# SCH_EDR_Project_2023-04-19.net
KiCad netlist of a schematic drawn in EasyEDA
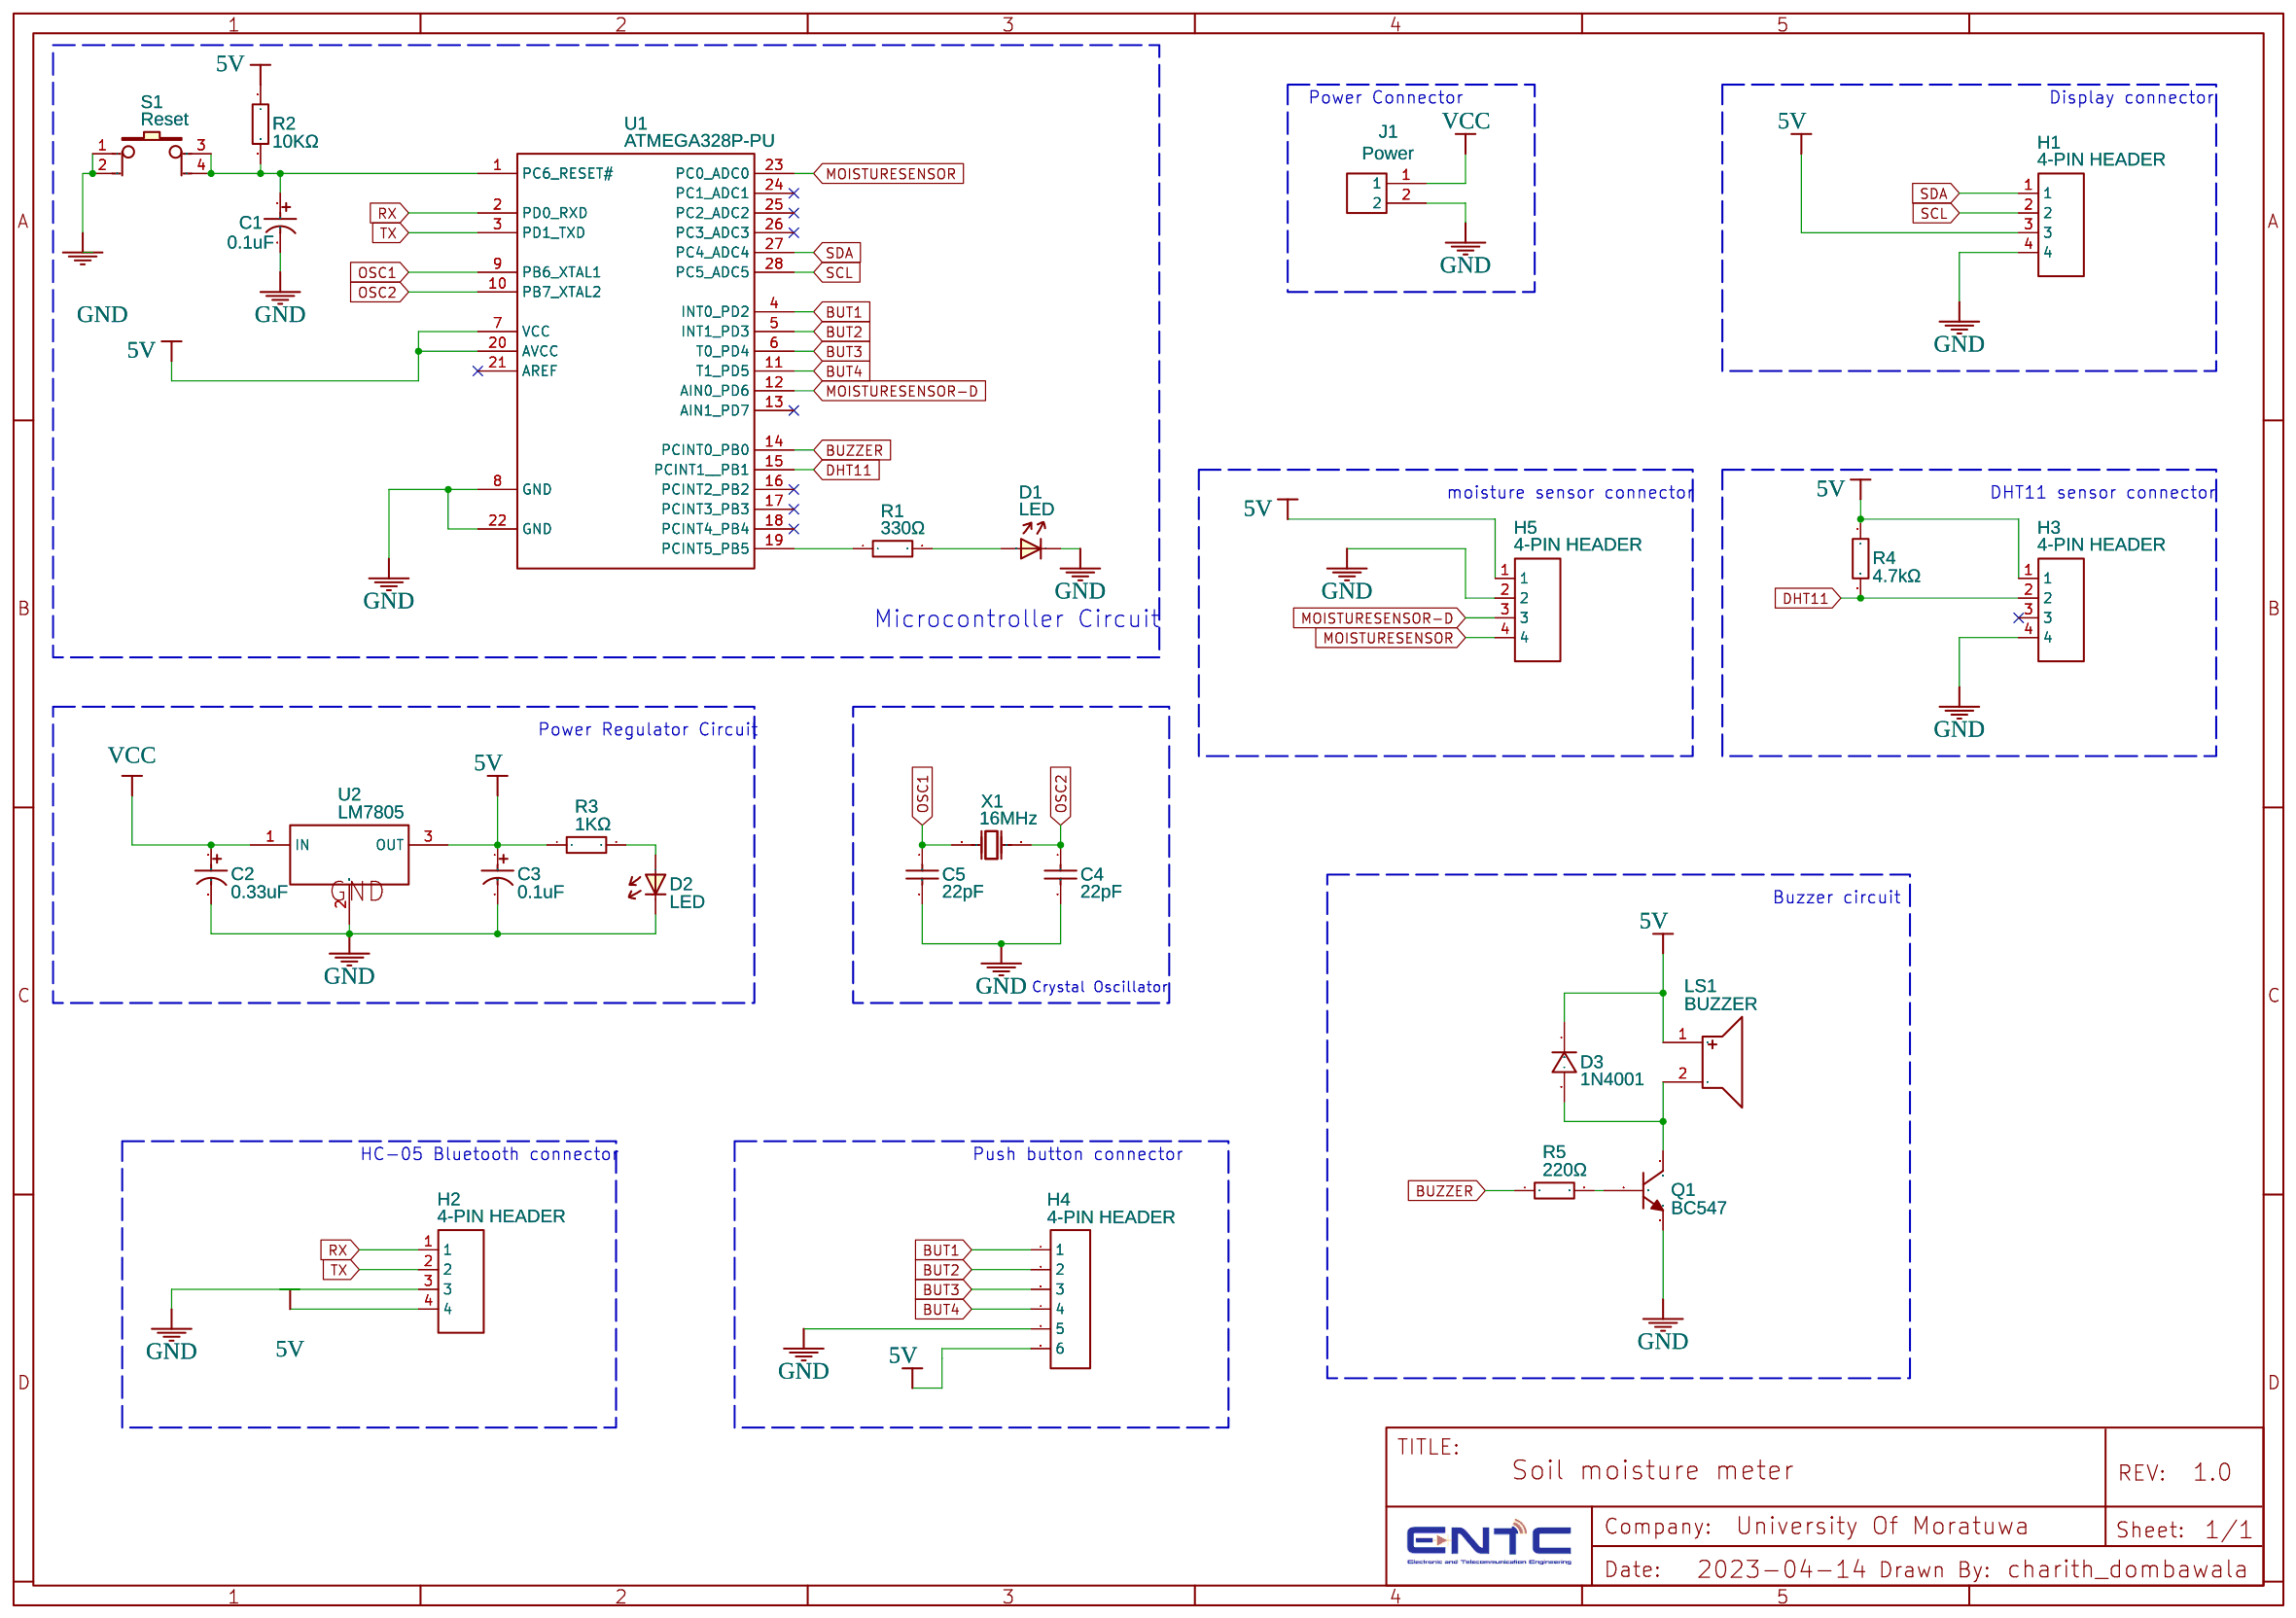
[diagram p0: schematic sheet]

(export (version "E")
  (design (tool "Eeschema 10.0.6"))
  (components
    (comp (ref "C1")
      (value "0.1uF")
      (fields (field (name "BOM_Manufacturer Part") "0.1UF 50V") (field (name "BOM_Supplier Part") "C28061"))
      (libsource (lib "") (part "0.1uF"))
    )
    (comp (ref "C2")
      (value "0.33uF")
      (fields
        (field (name "BOM_Manufacturer Part") "0.33uF 50V 5*11")
        (field (name "BOM_Supplier Part") "C45097")
      )
      (libsource (lib "") (part "0.33uF"))
    )
    (comp (ref "C3")
      (value "0.1uF")
      (fields (field (name "BOM_Manufacturer Part") "0.1UF 50V") (field (name "BOM_Supplier Part") "C28061"))
      (libsource (lib "") (part "0.1uF"))
    )
    (comp (ref "C4")
      (value "22pF")
      (fields
        (field (name "BOM_Manufacturer Part") "22pf/50V 10%")
        (field (name "BOM_Supplier Part") "C9316")
      )
      (libsource (lib "") (part "22pf/50V 10%"))
    )
    (comp (ref "C5")
      (value "22pF")
      (fields
        (field (name "BOM_Manufacturer Part") "22pf/50V 10%")
        (field (name "BOM_Supplier Part") "C9316")
      )
      (libsource (lib "") (part "22pf/50V 10%"))
    )
    (comp (ref "D1")
      (value "LED")
      (fields (field (name "Manufacturer Part") "5mm LED"))
      (libsource (lib "") (part "LED_1"))
    )
    (comp (ref "D2")
      (value "LED")
      (fields (field (name "Manufacturer Part") "5mm LED"))
      (libsource (lib "") (part "LED"))
    )
    (comp (ref "D3")
      (value "1N4001")
      (fields (field (name "BOM_Supplier Part") "C99656"))
      (libsource (lib "") (part "1N4001"))
    )
    (comp (ref "H1") (value "4-PIN HEADER") (libsource (lib "") (part "HEADER - HEADER-FEMALE-2.54_1X4")))
    (comp (ref "H2") (value "4-PIN HEADER") (libsource (lib "") (part "HEADER - HEADER-FEMALE-2.54_1X4")))
    (comp (ref "H3") (value "4-PIN HEADER") (libsource (lib "") (part "HEADER - HEADER-FEMALE-2.54_1X4")))
    (comp (ref "H4")
      (value "4-PIN HEADER")
      (fields (field (name "BOM_Supplier Part") "C40877"))
      (libsource (lib "") (part "HDR-F-2.54_1x6"))
    )
    (comp (ref "H5") (value "4-PIN HEADER") (libsource (lib "") (part "HEADER - HEADER-FEMALE-2.54_1X4")))
    (comp (ref "J1")
      (value "Power")
      (fields
        (field (name "BOM_Manufacturer Part") "XHB-2A Connector")
        (field (name "BOM_Supplier Part") "C57981")
      )
      (libsource (lib "") (part "JST_2 PIN"))
    )
    (comp (ref "LS1")
      (value "BUZZER")
      (fields
        (field (name "BOM_Manufacturer Part") "BUZZERHMB1206-03")
        (field (name "BOM_Supplier Part") "C96101")
      )
      (libsource (lib "") (part "BUZZER"))
    )
    (comp (ref "Q1")
      (value "BC547")
      (fields (field (name "BOM_Manufacturer Part") "BC547BTF") (field (name "BOM_Supplier Part") "C900798"))
      (libsource (lib "") (part "BC547BTF"))
    )
    (comp (ref "R1")
      (value "330Ω")
      (fields
        (field (name "BOM_Manufacturer Part") "MFR0W4F2200A50")
        (field (name "BOM_Supplier Part") "E57439")
      )
      (libsource (lib "") (part "RESISTOR"))
    )
    (comp (ref "R2")
      (value "10KΩ")
      (fields
        (field (name "BOM_Manufacturer Part") "MFR0W4F2200A50")
        (field (name "BOM_Supplier Part") "E57439")
      )
      (libsource (lib "") (part "RESISTOR_1"))
    )
    (comp (ref "R3")
      (value "1KΩ")
      (fields
        (field (name "BOM_Manufacturer Part") "MFR0W4F2200A50")
        (field (name "BOM_Supplier Part") "E57439")
      )
      (libsource (lib "") (part "RESISTOR"))
    )
    (comp (ref "R4")
      (value "4.7kΩ")
      (fields
        (field (name "BOM_Manufacturer Part") "MFR0W4F2200A50")
        (field (name "BOM_Supplier Part") "E57439")
      )
      (libsource (lib "") (part "RESISTOR_1"))
    )
    (comp (ref "R5")
      (value "220Ω")
      (fields
        (field (name "BOM_Manufacturer Part") "MFR0W4F2200A50")
        (field (name "BOM_Supplier Part") "E57439")
      )
      (libsource (lib "") (part "RESISTOR"))
    )
    (comp (ref "S1")
      (value "Reset")
      (fields
        (field (name "BOM_Manufacturer Part") "button6*6*8.5")
        (field (name "BOM_Supplier Part") "C59980")
      )
      (libsource (lib "") (part "Push_Button"))
    )
    (comp (ref "U1")
      (value "ATMEGA328P-PU")
      (fields (field (name "BOM_Supplier Part") "C33901"))
      (libsource (lib "") (part "ATMEGA328P-PU"))
    )
    (comp (ref "U2")
      (value "LM7805")
      (fields (field (name "BOM_Manufacturer Part") "L7805CV-DG") (field (name "BOM_Supplier Part") "C3795"))
      (libsource (lib "") (part "7805(TO-220)"))
    )
    (comp (ref "X1")
      (value "16MHz")
      (fields (field (name "BOM_Manufacturer Part") "ATS16A") (field (name "BOM_Supplier Part") "C1669847"))
      (libsource (lib "") (part "ATS16A"))
    )
  )
  (nets
    (net (code "1") (name "5V") (class "Default")
      (node (ref "C3") (pin "1") (pinfunction "1_1") (pintype "input"))
      (node (ref "D3") (pin "1") (pinfunction "C_1") (pintype "unspecified"))
      (node (ref "H1") (pin "3") (pinfunction "3_3") (pintype "unspecified"))
      (node (ref "H2") (pin "4") (pinfunction "4_4") (pintype "unspecified"))
      (node (ref "H3") (pin "1") (pinfunction "1_1") (pintype "unspecified"))
      (node (ref "H4") (pin "6") (pinfunction "6_6") (pintype "input"))
      (node (ref "H5") (pin "1") (pinfunction "1_1") (pintype "unspecified"))
      (node (ref "LS1") (pin "1") (pinfunction "1_1") (pintype "unspecified"))
      (node (ref "R2") (pin "1") (pinfunction "1_1") (pintype "input"))
      (node (ref "R3") (pin "1") (pinfunction "1_1") (pintype "input"))
      (node (ref "R4") (pin "1") (pinfunction "1_1") (pintype "input"))
      (node (ref "U1") (pin "20") (pinfunction "AVCC_20") (pintype "passive"))
      (node (ref "U1") (pin "7") (pinfunction "VCC_7") (pintype "passive"))
      (node (ref "U2") (pin "3") (pinfunction "OUT_3") (pintype "passive"))
    )
    (net (code "2") (name "BUT1") (class "Default")
      (node (ref "H4") (pin "1") (pinfunction "1_1") (pintype "input"))
      (node (ref "U1") (pin "4") (pinfunction "INT0_PD2_4") (pintype "bidirectional"))
    )
    (net (code "3") (name "BUT2") (class "Default")
      (node (ref "H4") (pin "2") (pinfunction "2_2") (pintype "input"))
      (node (ref "U1") (pin "5") (pinfunction "INT1_PD3_5") (pintype "bidirectional"))
    )
    (net (code "4") (name "BUT3") (class "Default")
      (node (ref "H4") (pin "3") (pinfunction "3_3") (pintype "input"))
      (node (ref "U1") (pin "6") (pinfunction "T0_PD4_6") (pintype "bidirectional"))
    )
    (net (code "5") (name "BUT4") (class "Default")
      (node (ref "H4") (pin "4") (pinfunction "4_4") (pintype "input"))
      (node (ref "U1") (pin "11") (pinfunction "T1_PD5_11") (pintype "bidirectional"))
    )
    (net (code "6") (name "BUZZER") (class "Default")
      (node (ref "R5") (pin "1") (pinfunction "1_1") (pintype "input"))
      (node (ref "U1") (pin "14") (pinfunction "PCINT0_PB0_14") (pintype "bidirectional"))
    )
    (net (code "7") (name "DHT11") (class "Default")
      (node (ref "H3") (pin "2") (pinfunction "2_2") (pintype "unspecified"))
      (node (ref "R4") (pin "2") (pinfunction "2_2") (pintype "input"))
      (node (ref "U1") (pin "15") (pinfunction "PCINT1__PB1_15") (pintype "bidirectional"))
    )
    (net (code "8") (name "GND") (class "Default")
      (node (ref "C1") (pin "2") (pinfunction "2_2") (pintype "input"))
      (node (ref "C2") (pin "2") (pinfunction "2_2") (pintype "input"))
      (node (ref "C3") (pin "2") (pinfunction "2_2") (pintype "input"))
      (node (ref "C4") (pin "2") (pinfunction "2_2") (pintype "input"))
      (node (ref "C5") (pin "2") (pinfunction "2_2") (pintype "input"))
      (node (ref "D1") (pin "2") (pinfunction "2_2") (pintype "unspecified"))
      (node (ref "D2") (pin "2") (pinfunction "2_2") (pintype "unspecified"))
      (node (ref "H1") (pin "4") (pinfunction "4_4") (pintype "unspecified"))
      (node (ref "H2") (pin "3") (pinfunction "3_3") (pintype "unspecified"))
      (node (ref "H3") (pin "4") (pinfunction "4_4") (pintype "unspecified"))
      (node (ref "H4") (pin "5") (pinfunction "5_5") (pintype "input"))
      (node (ref "H5") (pin "2") (pinfunction "2_2") (pintype "unspecified"))
      (node (ref "J1") (pin "2") (pinfunction "2_2") (pintype "unspecified"))
      (node (ref "Q1") (pin "3") (pinfunction "E_3") (pintype "unspecified"))
      (node (ref "S1") (pin "1") (pinfunction "1_1") (pintype "input"))
      (node (ref "S1") (pin "2") (pinfunction "2_2") (pintype "input"))
      (node (ref "U1") (pin "22") (pinfunction "GND_22") (pintype "passive"))
      (node (ref "U1") (pin "8") (pinfunction "GND_8") (pintype "passive"))
      (node (ref "U2") (pin "2") (pinfunction "GND_2") (pintype "passive"))
    )
    (net (code "9") (name "MOISTURESENSOR") (class "Default")
      (node (ref "H5") (pin "4") (pinfunction "4_4") (pintype "unspecified"))
      (node (ref "U1") (pin "23") (pinfunction "PC0_ADC0_23") (pintype "bidirectional"))
    )
    (net (code "10") (name "MOISTURESENSOR-D") (class "Default")
      (node (ref "H5") (pin "3") (pinfunction "3_3") (pintype "unspecified"))
      (node (ref "U1") (pin "12") (pinfunction "AIN0_PD6_12") (pintype "bidirectional"))
    )
    (net (code "11") (name "Net-(D1-Pad1)") (class "Default")
      (node (ref "D1") (pin "1") (pinfunction "1_1") (pintype "unspecified"))
      (node (ref "R1") (pin "2") (pinfunction "2_2") (pintype "input"))
    )
    (net (code "12") (name "Net-(D2-Pad1)") (class "Default")
      (node (ref "D2") (pin "1") (pinfunction "1_1") (pintype "unspecified"))
      (node (ref "R3") (pin "2") (pinfunction "2_2") (pintype "input"))
    )
    (net (code "13") (name "Net-(D3-A)") (class "Default")
      (node (ref "D3") (pin "2") (pinfunction "A_2") (pintype "unspecified"))
      (node (ref "LS1") (pin "2") (pinfunction "2_2") (pintype "unspecified"))
      (node (ref "Q1") (pin "1") (pinfunction "C_1") (pintype "unspecified"))
    )
    (net (code "14") (name "Net-(Q1-B)") (class "Default")
      (node (ref "Q1") (pin "2") (pinfunction "B_2") (pintype "unspecified"))
      (node (ref "R5") (pin "2") (pinfunction "2_2") (pintype "input"))
    )
    (net (code "15") (name "Net-(U1-PC6_RESET#)") (class "Default")
      (node (ref "C1") (pin "1") (pinfunction "1_1") (pintype "input"))
      (node (ref "R2") (pin "2") (pinfunction "2_2") (pintype "input"))
      (node (ref "S1") (pin "3") (pinfunction "3_3") (pintype "input"))
      (node (ref "S1") (pin "4") (pinfunction "4_4") (pintype "input"))
      (node (ref "U1") (pin "1") (pinfunction "PC6_RESET#_1") (pintype "bidirectional"))
    )
    (net (code "16") (name "Net-(U1-PCINT5_PB5)") (class "Default")
      (node (ref "R1") (pin "1") (pinfunction "1_1") (pintype "input"))
      (node (ref "U1") (pin "19") (pinfunction "PCINT5_PB5_19") (pintype "bidirectional"))
    )
    (net (code "17") (name "OSC1") (class "Default")
      (node (ref "C5") (pin "1") (pinfunction "1_1") (pintype "input"))
      (node (ref "U1") (pin "9") (pinfunction "PB6_XTAL1_9") (pintype "bidirectional"))
      (node (ref "X1") (pin "1") (pinfunction "1_1") (pintype "input"))
    )
    (net (code "18") (name "OSC2") (class "Default")
      (node (ref "C4") (pin "1") (pinfunction "1_1") (pintype "input"))
      (node (ref "U1") (pin "10") (pinfunction "PB7_XTAL2_10") (pintype "bidirectional"))
      (node (ref "X1") (pin "2") (pinfunction "2_2") (pintype "input"))
    )
    (net (code "19") (name "RX") (class "Default")
      (node (ref "H2") (pin "1") (pinfunction "1_1") (pintype "unspecified"))
      (node (ref "U1") (pin "2") (pinfunction "PD0_RXD_2") (pintype "bidirectional"))
    )
    (net (code "20") (name "SCL") (class "Default")
      (node (ref "H1") (pin "2") (pinfunction "2_2") (pintype "unspecified"))
      (node (ref "U1") (pin "28") (pinfunction "PC5_ADC5_28") (pintype "bidirectional"))
    )
    (net (code "21") (name "SDA") (class "Default")
      (node (ref "H1") (pin "1") (pinfunction "1_1") (pintype "unspecified"))
      (node (ref "U1") (pin "27") (pinfunction "PC4_ADC4_27") (pintype "bidirectional"))
    )
    (net (code "22") (name "TX") (class "Default")
      (node (ref "H2") (pin "2") (pinfunction "2_2") (pintype "unspecified"))
      (node (ref "U1") (pin "3") (pinfunction "PD1_TXD_3") (pintype "bidirectional"))
    )
    (net (code "23") (name "VCC") (class "Default")
      (node (ref "C2") (pin "1") (pinfunction "1_1") (pintype "input"))
      (node (ref "J1") (pin "1") (pinfunction "1_1") (pintype "unspecified"))
      (node (ref "U2") (pin "1") (pinfunction "IN_1") (pintype "passive"))
    )
    (net (code "24") (name "unconnected-(H3-Pad3)") (class "Default")
      (node (ref "H3") (pin "3") (pinfunction "3_3") (pintype "unspecified+no_connect"))
    )
    (net (code "25") (name "unconnected-(U1-AIN1_PD7-Pad13)") (class "Default")
      (node (ref "U1") (pin "13") (pinfunction "AIN1_PD7_13") (pintype "bidirectional+no_connect"))
    )
    (net (code "26") (name "unconnected-(U1-AREF-Pad21)") (class "Default")
      (node (ref "U1") (pin "21") (pinfunction "AREF_21") (pintype "passive+no_connect"))
    )
    (net (code "27") (name "unconnected-(U1-PC1_ADC1-Pad24)") (class "Default")
      (node (ref "U1") (pin "24") (pinfunction "PC1_ADC1_24") (pintype "bidirectional+no_connect"))
    )
    (net (code "28") (name "unconnected-(U1-PC2_ADC2-Pad25)") (class "Default")
      (node (ref "U1") (pin "25") (pinfunction "PC2_ADC2_25") (pintype "bidirectional+no_connect"))
    )
    (net (code "29") (name "unconnected-(U1-PC3_ADC3-Pad26)") (class "Default")
      (node (ref "U1") (pin "26") (pinfunction "PC3_ADC3_26") (pintype "bidirectional+no_connect"))
    )
    (net (code "30") (name "unconnected-(U1-PCINT2_PB2-Pad16)") (class "Default")
      (node (ref "U1") (pin "16") (pinfunction "PCINT2_PB2_16") (pintype "bidirectional+no_connect"))
    )
    (net (code "31") (name "unconnected-(U1-PCINT3_PB3-Pad17)") (class "Default")
      (node (ref "U1") (pin "17") (pinfunction "PCINT3_PB3_17") (pintype "bidirectional+no_connect"))
    )
    (net (code "32") (name "unconnected-(U1-PCINT4_PB4-Pad18)") (class "Default")
      (node (ref "U1") (pin "18") (pinfunction "PCINT4_PB4_18") (pintype "bidirectional+no_connect"))
    )
  )
)
